# MainLAN_ARM.net
KiCad netlist of a schematic drawn in EAGLE
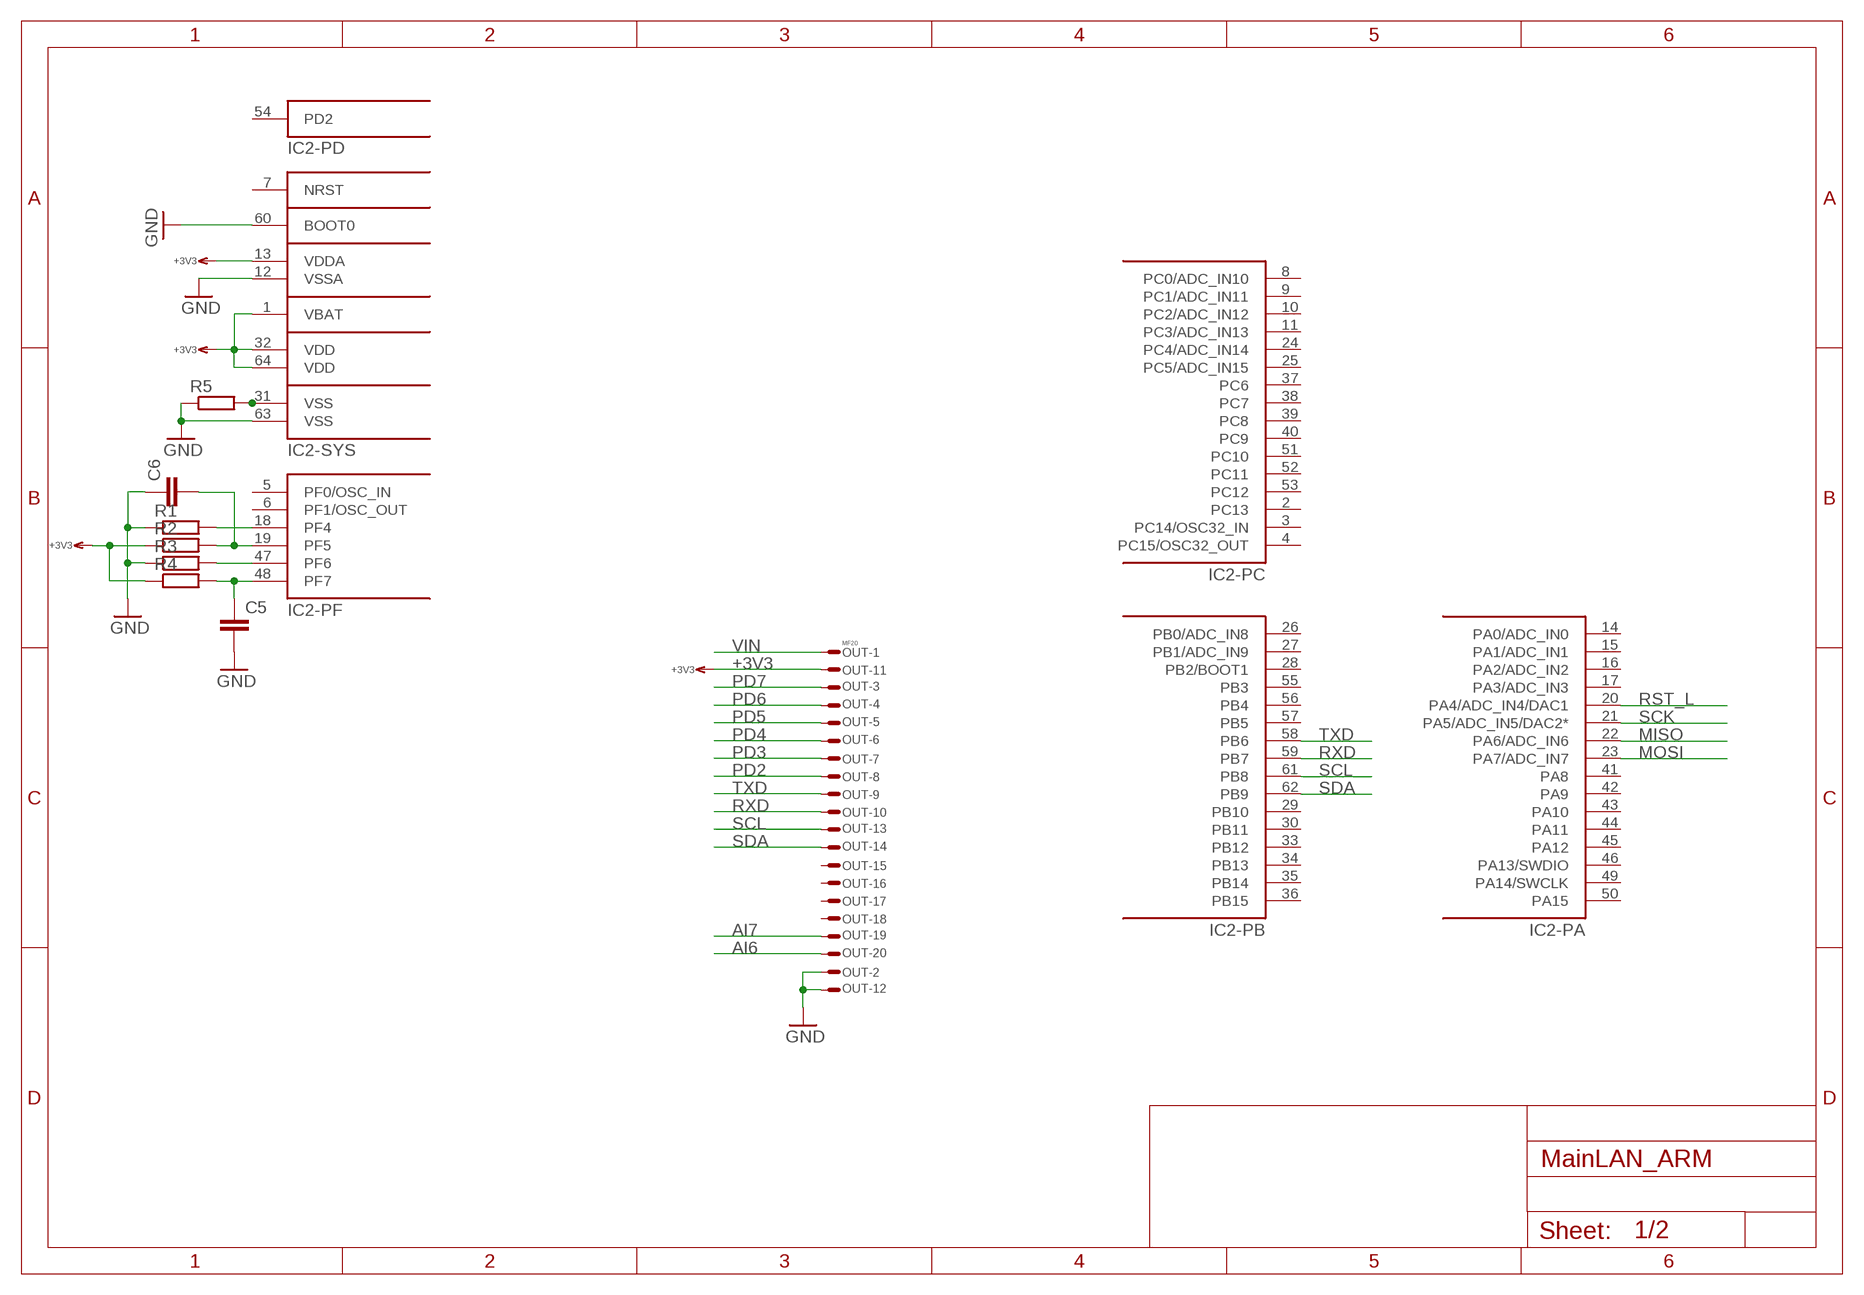
[diagram p0: schematic, sheet 1]
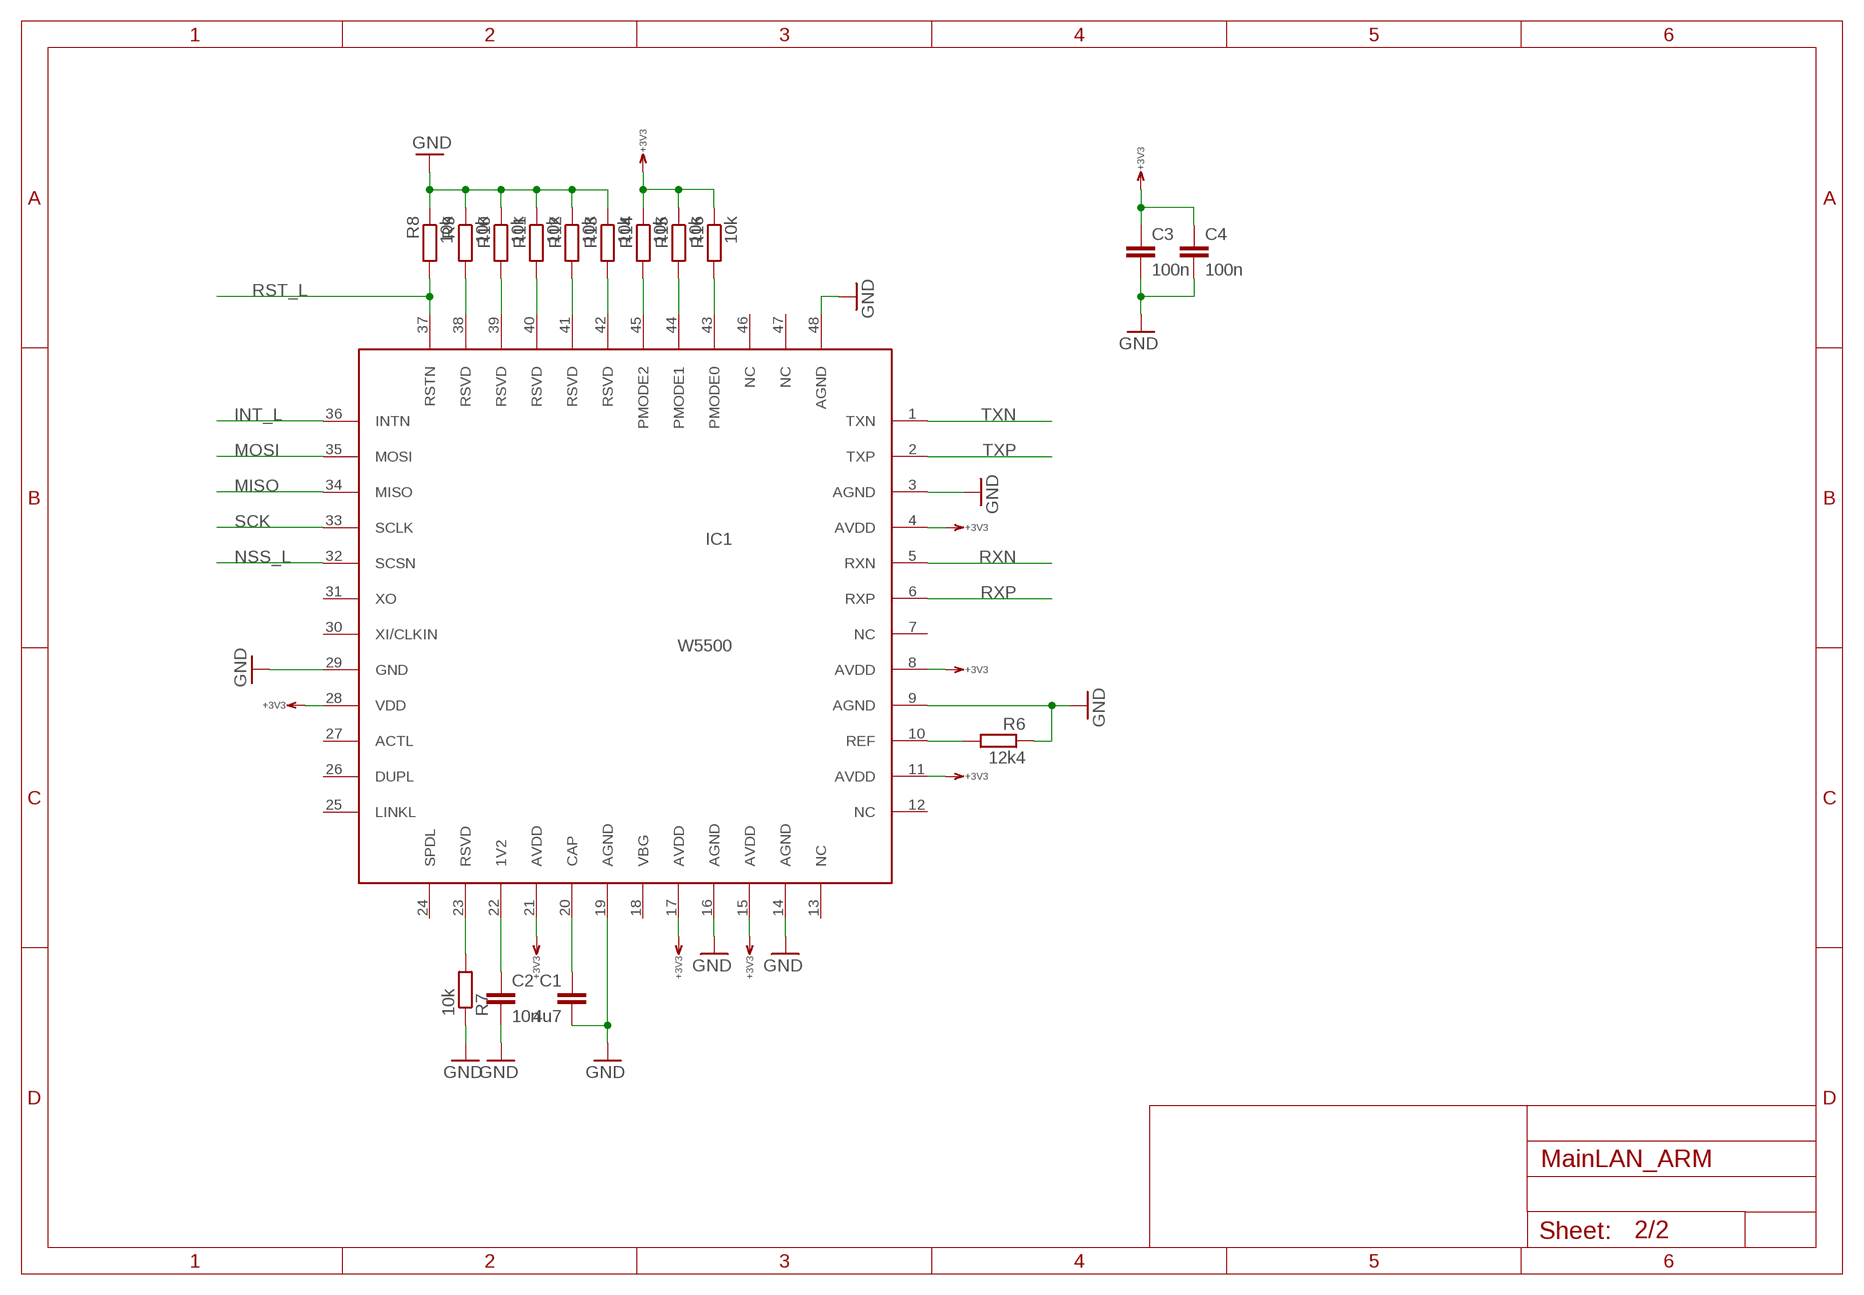
[diagram p1: schematic, sheet 2]

(export (version "E")
  (design (tool "Eeschema 10.0.6"))
  (components
    (comp (ref "C1")
      (value "4u7")
      (footprint "eagle-import:0402")
      (libsource (lib "eagle-import") (part "C0402"))
    )
    (comp (ref "C2")
      (value "10n")
      (footprint "eagle-import:0402")
      (libsource (lib "eagle-import") (part "C0402"))
    )
    (comp (ref "C3")
      (value "100n")
      (footprint "eagle-import:0402")
      (libsource (lib "eagle-import") (part "C0402"))
    )
    (comp (ref "C4")
      (value "100n")
      (footprint "eagle-import:0402")
      (libsource (lib "eagle-import") (part "C0402"))
    )
    (comp (ref "IC1")
      (value "W5500")
      (footprint "eagle-import:LQFP48")
      (libsource (lib "eagle-import") (part "W5500"))
    )
    (comp (ref "R6")
      (value "12k4")
      (footprint "eagle-import:0402")
      (libsource (lib "eagle-import") (part "R0402"))
    )
    (comp (ref "R7")
      (value "10k")
      (footprint "eagle-import:0402")
      (libsource (lib "eagle-import") (part "R0402"))
    )
    (comp (ref "R8")
      (value "10k")
      (footprint "eagle-import:0402")
      (libsource (lib "eagle-import") (part "R0402"))
    )
    (comp (ref "R9")
      (value "10k")
      (footprint "eagle-import:0402")
      (libsource (lib "eagle-import") (part "R0402"))
    )
    (comp (ref "R10")
      (value "10k")
      (footprint "eagle-import:0402")
      (libsource (lib "eagle-import") (part "R0402"))
    )
    (comp (ref "R11")
      (value "10k")
      (footprint "eagle-import:0402")
      (libsource (lib "eagle-import") (part "R0402"))
    )
    (comp (ref "R12")
      (value "10k")
      (footprint "eagle-import:0402")
      (libsource (lib "eagle-import") (part "R0402"))
    )
    (comp (ref "R13")
      (value "10k")
      (footprint "eagle-import:0402")
      (libsource (lib "eagle-import") (part "R0402"))
    )
    (comp (ref "R14")
      (value "10k")
      (footprint "eagle-import:0402")
      (libsource (lib "eagle-import") (part "R0402"))
    )
    (comp (ref "R15")
      (value "10k")
      (footprint "eagle-import:0402")
      (libsource (lib "eagle-import") (part "R0402"))
    )
    (comp (ref "R16")
      (value "10k")
      (footprint "eagle-import:0402")
      (libsource (lib "eagle-import") (part "R0402"))
    )
    (comp (ref "C5")
      (value "C0402")
      (footprint "eagle-import:0402")
      (libsource (lib "eagle-import") (part "C0402"))
    )
    (comp (ref "C6")
      (value "C0402")
      (footprint "eagle-import:0402")
      (libsource (lib "eagle-import") (part "C0402"))
    )
    (comp (ref "IC2")
      (value "STM32F0__R")
      (footprint "eagle-import:LQFP64")
      (libsource (lib "eagle-import") (part "STM32F0__R"))
    )
    (comp (ref "OUT")
      (value "MF20")
      (footprint "eagle-import:ML20LS")
      (libsource (lib "eagle-import") (part "ML20?ELS"))
    )
    (comp (ref "R1")
      (value "R0402")
      (footprint "eagle-import:0402")
      (libsource (lib "eagle-import") (part "R0402"))
    )
    (comp (ref "R2")
      (value "R0402")
      (footprint "eagle-import:0402")
      (libsource (lib "eagle-import") (part "R0402"))
    )
    (comp (ref "R3")
      (value "R0603")
      (footprint "eagle-import:0603")
      (libsource (lib "eagle-import") (part "R0603"))
    )
    (comp (ref "R4")
      (value "R0603")
      (footprint "eagle-import:0603")
      (libsource (lib "eagle-import") (part "R0603"))
    )
    (comp (ref "R5")
      (value "R0603")
      (footprint "eagle-import:0603")
      (libsource (lib "eagle-import") (part "R0603"))
    )
  )
  (nets
    (net (code "1") (name "+3V3") (class "Default")
      (node (ref "C3") (pin "1") (pinfunction "1_1") (pintype "passive"))
      (node (ref "C4") (pin "1") (pinfunction "1_1") (pintype "passive"))
      (node (ref "IC1") (pin "11") (pinfunction "AVDD_11") (pintype "bidirectional"))
      (node (ref "IC1") (pin "15") (pinfunction "AVDD_15") (pintype "bidirectional"))
      (node (ref "IC1") (pin "17") (pinfunction "AVDD_17") (pintype "bidirectional"))
      (node (ref "IC1") (pin "21") (pinfunction "AVDD_21") (pintype "bidirectional"))
      (node (ref "IC1") (pin "28") (pinfunction "VDD_28") (pintype "bidirectional"))
      (node (ref "IC1") (pin "4") (pinfunction "AVDD_4") (pintype "bidirectional"))
      (node (ref "IC1") (pin "8") (pinfunction "AVDD_8") (pintype "bidirectional"))
      (node (ref "IC2") (pin "1") (pinfunction "VBAT_1") (pintype "bidirectional"))
      (node (ref "IC2") (pin "13") (pinfunction "VDDA_13") (pintype "bidirectional"))
      (node (ref "IC2") (pin "32") (pinfunction "VDD_32") (pintype "bidirectional"))
      (node (ref "IC2") (pin "64") (pinfunction "VDD_64") (pintype "bidirectional"))
      (node (ref "OUT") (pin "P$11") (pinfunction "S_P$11") (pintype "passive"))
      (node (ref "R14") (pin "1") (pinfunction "1_1") (pintype "passive"))
      (node (ref "R15") (pin "1") (pinfunction "1_1") (pintype "passive"))
      (node (ref "R16") (pin "1") (pinfunction "1_1") (pintype "passive"))
      (node (ref "R2") (pin "1") (pinfunction "1_1") (pintype "passive"))
      (node (ref "R4") (pin "1") (pinfunction "1_1") (pintype "passive"))
    )
    (net (code "2") (name "AI6") (class "Default")
      (node (ref "OUT") (pin "P$20") (pinfunction "S_P$20") (pintype "passive"))
    )
    (net (code "3") (name "AI7") (class "Default")
      (node (ref "OUT") (pin "P$19") (pinfunction "S_P$19") (pintype "passive"))
    )
    (net (code "4") (name "GND") (class "Default")
      (node (ref "C1") (pin "2") (pinfunction "2_2") (pintype "passive"))
      (node (ref "C2") (pin "2") (pinfunction "2_2") (pintype "passive"))
      (node (ref "C3") (pin "2") (pinfunction "2_2") (pintype "passive"))
      (node (ref "C4") (pin "2") (pinfunction "2_2") (pintype "passive"))
      (node (ref "C5") (pin "2") (pinfunction "2_2") (pintype "passive"))
      (node (ref "C6") (pin "1") (pinfunction "1_1") (pintype "passive"))
      (node (ref "IC1") (pin "14") (pinfunction "AGND_14") (pintype "bidirectional"))
      (node (ref "IC1") (pin "16") (pinfunction "AGND_16") (pintype "bidirectional"))
      (node (ref "IC1") (pin "19") (pinfunction "AGND_19") (pintype "bidirectional"))
      (node (ref "IC1") (pin "29") (pinfunction "GND_29") (pintype "bidirectional"))
      (node (ref "IC1") (pin "3") (pinfunction "AGND_3") (pintype "bidirectional"))
      (node (ref "IC1") (pin "48") (pinfunction "AGND_48") (pintype "bidirectional"))
      (node (ref "IC1") (pin "9") (pinfunction "AGND_9") (pintype "bidirectional"))
      (node (ref "IC2") (pin "12") (pinfunction "VSSA_12") (pintype "bidirectional"))
      (node (ref "IC2") (pin "60") (pinfunction "BOOT0_60") (pintype "bidirectional"))
      (node (ref "IC2") (pin "63") (pinfunction "VSS_63") (pintype "bidirectional"))
      (node (ref "OUT") (pin "P$12") (pinfunction "S_P$12") (pintype "passive"))
      (node (ref "OUT") (pin "P$2") (pinfunction "S_P$2") (pintype "passive"))
      (node (ref "R1") (pin "1") (pinfunction "1_1") (pintype "passive"))
      (node (ref "R10") (pin "1") (pinfunction "1_1") (pintype "passive"))
      (node (ref "R11") (pin "1") (pinfunction "1_1") (pintype "passive"))
      (node (ref "R12") (pin "1") (pinfunction "1_1") (pintype "passive"))
      (node (ref "R13") (pin "1") (pinfunction "1_1") (pintype "passive"))
      (node (ref "R3") (pin "1") (pinfunction "1_1") (pintype "passive"))
      (node (ref "R5") (pin "1") (pinfunction "1_1") (pintype "passive"))
      (node (ref "R6") (pin "1") (pinfunction "1_1") (pintype "passive"))
      (node (ref "R7") (pin "1") (pinfunction "1_1") (pintype "passive"))
      (node (ref "R8") (pin "1") (pinfunction "1_1") (pintype "passive"))
      (node (ref "R9") (pin "1") (pinfunction "1_1") (pintype "passive"))
    )
    (net (code "5") (name "INT_L") (class "Default")
      (node (ref "IC1") (pin "36") (pinfunction "INTN_36") (pintype "output"))
    )
    (net (code "6") (name "MISO") (class "Default")
      (node (ref "IC1") (pin "34") (pinfunction "MISO_34") (pintype "output"))
      (node (ref "IC2") (pin "22") (pinfunction "PA6/ADC_IN6_22") (pintype "bidirectional"))
    )
    (net (code "7") (name "MOSI") (class "Default")
      (node (ref "IC1") (pin "35") (pinfunction "MOSI_35") (pintype "input"))
      (node (ref "IC2") (pin "23") (pinfunction "PA7/ADC_IN7_23") (pintype "bidirectional"))
    )
    (net (code "8") (name "NSS_L") (class "Default")
      (node (ref "IC1") (pin "32") (pinfunction "SCSN_32") (pintype "input"))
    )
    (net (code "9") (name "Net-(IC1-1V2)") (class "Default")
      (node (ref "C2") (pin "1") (pinfunction "1_1") (pintype "passive"))
      (node (ref "IC1") (pin "22") (pinfunction "1V2_22") (pintype "bidirectional"))
    )
    (net (code "10") (name "Net-(IC1-CAP)") (class "Default")
      (node (ref "C1") (pin "1") (pinfunction "1_1") (pintype "passive"))
      (node (ref "IC1") (pin "20") (pinfunction "CAP_20") (pintype "output"))
    )
    (net (code "11") (name "Net-(IC1-PMODE0)") (class "Default")
      (node (ref "IC1") (pin "43") (pinfunction "PMODE0_43") (pintype "input"))
      (node (ref "R16") (pin "2") (pinfunction "2_2") (pintype "passive"))
    )
    (net (code "12") (name "Net-(IC1-PMODE1)") (class "Default")
      (node (ref "IC1") (pin "44") (pinfunction "PMODE1_44") (pintype "input"))
      (node (ref "R15") (pin "2") (pinfunction "2_2") (pintype "passive"))
    )
    (net (code "13") (name "Net-(IC1-PMODE2)") (class "Default")
      (node (ref "IC1") (pin "45") (pinfunction "PMODE2_45") (pintype "input"))
      (node (ref "R14") (pin "2") (pinfunction "2_2") (pintype "passive"))
    )
    (net (code "14") (name "Net-(IC1-REF)") (class "Default")
      (node (ref "IC1") (pin "10") (pinfunction "REF_10") (pintype "bidirectional"))
      (node (ref "R6") (pin "2") (pinfunction "2_2") (pintype "passive"))
    )
    (net (code "15") (name "Net-(IC1-RSVD-Pad23)") (class "Default")
      (node (ref "IC1") (pin "23") (pinfunction "RSVD_23") (pintype "input"))
      (node (ref "R7") (pin "2") (pinfunction "2_2") (pintype "passive"))
    )
    (net (code "16") (name "Net-(IC1-RSVD-Pad38)") (class "Default")
      (node (ref "IC1") (pin "38") (pinfunction "RSVD_38") (pintype "input"))
      (node (ref "R9") (pin "2") (pinfunction "2_2") (pintype "passive"))
    )
    (net (code "17") (name "Net-(IC1-RSVD-Pad39)") (class "Default")
      (node (ref "IC1") (pin "39") (pinfunction "RSVD_39") (pintype "input"))
      (node (ref "R10") (pin "2") (pinfunction "2_2") (pintype "passive"))
    )
    (net (code "18") (name "Net-(IC1-RSVD-Pad40)") (class "Default")
      (node (ref "IC1") (pin "40") (pinfunction "RSVD_40") (pintype "input"))
      (node (ref "R11") (pin "2") (pinfunction "2_2") (pintype "passive"))
    )
    (net (code "19") (name "Net-(IC1-RSVD-Pad41)") (class "Default")
      (node (ref "IC1") (pin "41") (pinfunction "RSVD_41") (pintype "input"))
      (node (ref "R12") (pin "2") (pinfunction "2_2") (pintype "passive"))
    )
    (net (code "20") (name "Net-(IC1-RSVD-Pad42)") (class "Default")
      (node (ref "IC1") (pin "42") (pinfunction "RSVD_42") (pintype "input"))
      (node (ref "R13") (pin "2") (pinfunction "2_2") (pintype "passive"))
    )
    (net (code "21") (name "Net-(IC2E-PF4)") (class "Default")
      (node (ref "IC2") (pin "18") (pinfunction "PF4_18") (pintype "bidirectional"))
      (node (ref "R1") (pin "2") (pinfunction "2_2") (pintype "passive"))
    )
    (net (code "22") (name "Net-(IC2E-PF5)") (class "Default")
      (node (ref "C6") (pin "2") (pinfunction "2_2") (pintype "passive"))
      (node (ref "IC2") (pin "19") (pinfunction "PF5_19") (pintype "bidirectional"))
      (node (ref "R2") (pin "2") (pinfunction "2_2") (pintype "passive"))
    )
    (net (code "23") (name "Net-(IC2E-PF6)") (class "Default")
      (node (ref "IC2") (pin "47") (pinfunction "PF6_47") (pintype "bidirectional"))
      (node (ref "R3") (pin "2") (pinfunction "2_2") (pintype "passive"))
    )
    (net (code "24") (name "Net-(IC2E-PF7)") (class "Default")
      (node (ref "C5") (pin "1") (pinfunction "1_1") (pintype "passive"))
      (node (ref "IC2") (pin "48") (pinfunction "PF7_48") (pintype "bidirectional"))
      (node (ref "R4") (pin "2") (pinfunction "2_2") (pintype "passive"))
    )
    (net (code "25") (name "Net-(IC2F-VSS-Pad31)") (class "Default")
      (node (ref "IC2") (pin "31") (pinfunction "VSS_31") (pintype "bidirectional"))
      (node (ref "R5") (pin "2") (pinfunction "2_2") (pintype "passive"))
    )
    (net (code "26") (name "PD2") (class "Default")
      (node (ref "OUT") (pin "P$8") (pinfunction "S_P$8") (pintype "passive"))
    )
    (net (code "27") (name "PD3") (class "Default")
      (node (ref "OUT") (pin "P$7") (pinfunction "S_P$7") (pintype "passive"))
    )
    (net (code "28") (name "PD4") (class "Default")
      (node (ref "OUT") (pin "P$6") (pinfunction "S_P$6") (pintype "passive"))
    )
    (net (code "29") (name "PD5") (class "Default")
      (node (ref "OUT") (pin "P$5") (pinfunction "S_P$5") (pintype "passive"))
    )
    (net (code "30") (name "PD6") (class "Default")
      (node (ref "OUT") (pin "P$4") (pinfunction "S_P$4") (pintype "passive"))
    )
    (net (code "31") (name "PD7") (class "Default")
      (node (ref "OUT") (pin "P$3") (pinfunction "S_P$3") (pintype "passive"))
    )
    (net (code "32") (name "RST_L") (class "Default")
      (node (ref "IC1") (pin "37") (pinfunction "RSTN_37") (pintype "input"))
      (node (ref "IC2") (pin "20") (pinfunction "PA4/ADC_IN4/DAC1_20") (pintype "bidirectional"))
      (node (ref "R8") (pin "2") (pinfunction "2_2") (pintype "passive"))
    )
    (net (code "33") (name "RXD") (class "Default")
      (node (ref "IC2") (pin "59") (pinfunction "PB7_59") (pintype "bidirectional"))
      (node (ref "OUT") (pin "P$10") (pinfunction "S_P$10") (pintype "passive"))
    )
    (net (code "34") (name "RXN") (class "Default")
      (node (ref "IC1") (pin "5") (pinfunction "RXN_5") (pintype "input"))
    )
    (net (code "35") (name "RXP") (class "Default")
      (node (ref "IC1") (pin "6") (pinfunction "RXP_6") (pintype "input"))
    )
    (net (code "36") (name "SCK") (class "Default")
      (node (ref "IC1") (pin "33") (pinfunction "SCLK_33") (pintype "input"))
      (node (ref "IC2") (pin "21") (pinfunction "PA5/ADC_IN5/DAC2*_21") (pintype "bidirectional"))
    )
    (net (code "37") (name "SCL") (class "Default")
      (node (ref "IC2") (pin "61") (pinfunction "PB8_61") (pintype "bidirectional"))
      (node (ref "OUT") (pin "P$13") (pinfunction "S_P$13") (pintype "passive"))
    )
    (net (code "38") (name "SDA") (class "Default")
      (node (ref "IC2") (pin "62") (pinfunction "PB9_62") (pintype "bidirectional"))
      (node (ref "OUT") (pin "P$14") (pinfunction "S_P$14") (pintype "passive"))
    )
    (net (code "39") (name "TXD") (class "Default")
      (node (ref "IC2") (pin "58") (pinfunction "PB6_58") (pintype "bidirectional"))
      (node (ref "OUT") (pin "P$9") (pinfunction "S_P$9") (pintype "passive"))
    )
    (net (code "40") (name "TXN") (class "Default")
      (node (ref "IC1") (pin "1") (pinfunction "TXN_1") (pintype "output"))
    )
    (net (code "41") (name "TXP") (class "Default")
      (node (ref "IC1") (pin "2") (pinfunction "TXP_2") (pintype "output"))
    )
    (net (code "42") (name "VIN") (class "Default")
      (node (ref "OUT") (pin "P$1") (pinfunction "S_P$1") (pintype "passive"))
    )
    (net (code "43") (name "unconnected-(IC1-ACTL-Pad27)") (class "Default")
      (node (ref "IC1") (pin "27") (pinfunction "ACTL_27") (pintype "output"))
    )
    (net (code "44") (name "unconnected-(IC1-DUPL-Pad26)") (class "Default")
      (node (ref "IC1") (pin "26") (pinfunction "DUPL_26") (pintype "output"))
    )
    (net (code "45") (name "unconnected-(IC1-LINKL-Pad25)") (class "Default")
      (node (ref "IC1") (pin "25") (pinfunction "LINKL_25") (pintype "output"))
    )
    (net (code "46") (name "unconnected-(IC1-NC-Pad7)") (class "Default")
      (node (ref "IC1") (pin "7") (pinfunction "NC_7") (pintype "no_connect"))
    )
    (net (code "47") (name "unconnected-(IC1-NC-Pad12)") (class "Default")
      (node (ref "IC1") (pin "12") (pinfunction "NC_12") (pintype "no_connect"))
    )
    (net (code "48") (name "unconnected-(IC1-NC-Pad13)") (class "Default")
      (node (ref "IC1") (pin "13") (pinfunction "NC_13") (pintype "no_connect"))
    )
    (net (code "49") (name "unconnected-(IC1-NC-Pad46)") (class "Default")
      (node (ref "IC1") (pin "46") (pinfunction "NC_46") (pintype "no_connect"))
    )
    (net (code "50") (name "unconnected-(IC1-NC-Pad47)") (class "Default")
      (node (ref "IC1") (pin "47") (pinfunction "NC_47") (pintype "no_connect"))
    )
    (net (code "51") (name "unconnected-(IC1-SPDL-Pad24)") (class "Default")
      (node (ref "IC1") (pin "24") (pinfunction "SPDL_24") (pintype "output"))
    )
    (net (code "52") (name "unconnected-(IC1-VBG-Pad18)") (class "Default")
      (node (ref "IC1") (pin "18") (pinfunction "VBG_18") (pintype "output"))
    )
    (net (code "53") (name "unconnected-(IC1-XI{slash}CLKIN-Pad30)") (class "Default")
      (node (ref "IC1") (pin "30") (pinfunction "XI/CLKIN_30") (pintype "input"))
    )
    (net (code "54") (name "unconnected-(IC1-XO-Pad31)") (class "Default")
      (node (ref "IC1") (pin "31") (pinfunction "XO_31") (pintype "output"))
    )
    (net (code "55") (name "unconnected-(IC2A-PA0{slash}ADC_IN0-Pad14)") (class "Default")
      (node (ref "IC2") (pin "14") (pinfunction "PA0/ADC_IN0_14") (pintype "bidirectional"))
    )
    (net (code "56") (name "unconnected-(IC2A-PA1{slash}ADC_IN1-Pad15)") (class "Default")
      (node (ref "IC2") (pin "15") (pinfunction "PA1/ADC_IN1_15") (pintype "bidirectional"))
    )
    (net (code "57") (name "unconnected-(IC2A-PA2{slash}ADC_IN2-Pad16)") (class "Default")
      (node (ref "IC2") (pin "16") (pinfunction "PA2/ADC_IN2_16") (pintype "bidirectional"))
    )
    (net (code "58") (name "unconnected-(IC2A-PA3{slash}ADC_IN3-Pad17)") (class "Default")
      (node (ref "IC2") (pin "17") (pinfunction "PA3/ADC_IN3_17") (pintype "bidirectional"))
    )
    (net (code "59") (name "unconnected-(IC2A-PA8-Pad41)") (class "Default")
      (node (ref "IC2") (pin "41") (pinfunction "PA8_41") (pintype "bidirectional"))
    )
    (net (code "60") (name "unconnected-(IC2A-PA9-Pad42)") (class "Default")
      (node (ref "IC2") (pin "42") (pinfunction "PA9_42") (pintype "bidirectional"))
    )
    (net (code "61") (name "unconnected-(IC2A-PA10-Pad43)") (class "Default")
      (node (ref "IC2") (pin "43") (pinfunction "PA10_43") (pintype "bidirectional"))
    )
    (net (code "62") (name "unconnected-(IC2A-PA11-Pad44)") (class "Default")
      (node (ref "IC2") (pin "44") (pinfunction "PA11_44") (pintype "bidirectional"))
    )
    (net (code "63") (name "unconnected-(IC2A-PA12-Pad45)") (class "Default")
      (node (ref "IC2") (pin "45") (pinfunction "PA12_45") (pintype "bidirectional"))
    )
    (net (code "64") (name "unconnected-(IC2A-PA13{slash}SWDIO-Pad46)") (class "Default")
      (node (ref "IC2") (pin "46") (pinfunction "PA13/SWDIO_46") (pintype "bidirectional"))
    )
    (net (code "65") (name "unconnected-(IC2A-PA14{slash}SWCLK-Pad49)") (class "Default")
      (node (ref "IC2") (pin "49") (pinfunction "PA14/SWCLK_49") (pintype "bidirectional"))
    )
    (net (code "66") (name "unconnected-(IC2A-PA15-Pad50)") (class "Default")
      (node (ref "IC2") (pin "50") (pinfunction "PA15_50") (pintype "bidirectional"))
    )
    (net (code "67") (name "unconnected-(IC2B-PB0{slash}ADC_IN8-Pad26)") (class "Default")
      (node (ref "IC2") (pin "26") (pinfunction "PB0/ADC_IN8_26") (pintype "bidirectional"))
    )
    (net (code "68") (name "unconnected-(IC2B-PB1{slash}ADC_IN9-Pad27)") (class "Default")
      (node (ref "IC2") (pin "27") (pinfunction "PB1/ADC_IN9_27") (pintype "bidirectional"))
    )
    (net (code "69") (name "unconnected-(IC2B-PB2{slash}BOOT1-Pad28)") (class "Default")
      (node (ref "IC2") (pin "28") (pinfunction "PB2/BOOT1_28") (pintype "bidirectional"))
    )
    (net (code "70") (name "unconnected-(IC2B-PB3-Pad55)") (class "Default")
      (node (ref "IC2") (pin "55") (pinfunction "PB3_55") (pintype "bidirectional"))
    )
    (net (code "71") (name "unconnected-(IC2B-PB4-Pad56)") (class "Default")
      (node (ref "IC2") (pin "56") (pinfunction "PB4_56") (pintype "bidirectional"))
    )
    (net (code "72") (name "unconnected-(IC2B-PB5-Pad57)") (class "Default")
      (node (ref "IC2") (pin "57") (pinfunction "PB5_57") (pintype "bidirectional"))
    )
    (net (code "73") (name "unconnected-(IC2B-PB10-Pad29)") (class "Default")
      (node (ref "IC2") (pin "29") (pinfunction "PB10_29") (pintype "bidirectional"))
    )
    (net (code "74") (name "unconnected-(IC2B-PB11-Pad30)") (class "Default")
      (node (ref "IC2") (pin "30") (pinfunction "PB11_30") (pintype "bidirectional"))
    )
    (net (code "75") (name "unconnected-(IC2B-PB12-Pad33)") (class "Default")
      (node (ref "IC2") (pin "33") (pinfunction "PB12_33") (pintype "bidirectional"))
    )
    (net (code "76") (name "unconnected-(IC2B-PB13-Pad34)") (class "Default")
      (node (ref "IC2") (pin "34") (pinfunction "PB13_34") (pintype "bidirectional"))
    )
    (net (code "77") (name "unconnected-(IC2B-PB14-Pad35)") (class "Default")
      (node (ref "IC2") (pin "35") (pinfunction "PB14_35") (pintype "bidirectional"))
    )
    (net (code "78") (name "unconnected-(IC2B-PB15-Pad36)") (class "Default")
      (node (ref "IC2") (pin "36") (pinfunction "PB15_36") (pintype "bidirectional"))
    )
    (net (code "79") (name "unconnected-(IC2C-PC0{slash}ADC_IN10-Pad8)") (class "Default")
      (node (ref "IC2") (pin "8") (pinfunction "PC0/ADC_IN10_8") (pintype "bidirectional"))
    )
    (net (code "80") (name "unconnected-(IC2C-PC1{slash}ADC_IN11-Pad9)") (class "Default")
      (node (ref "IC2") (pin "9") (pinfunction "PC1/ADC_IN11_9") (pintype "bidirectional"))
    )
    (net (code "81") (name "unconnected-(IC2C-PC2{slash}ADC_IN12-Pad10)") (class "Default")
      (node (ref "IC2") (pin "10") (pinfunction "PC2/ADC_IN12_10") (pintype "bidirectional"))
    )
    (net (code "82") (name "unconnected-(IC2C-PC3{slash}ADC_IN13-Pad11)") (class "Default")
      (node (ref "IC2") (pin "11") (pinfunction "PC3/ADC_IN13_11") (pintype "bidirectional"))
    )
    (net (code "83") (name "unconnected-(IC2C-PC4{slash}ADC_IN14-Pad24)") (class "Default")
      (node (ref "IC2") (pin "24") (pinfunction "PC4/ADC_IN14_24") (pintype "bidirectional"))
    )
    (net (code "84") (name "unconnected-(IC2C-PC5{slash}ADC_IN15-Pad25)") (class "Default")
      (node (ref "IC2") (pin "25") (pinfunction "PC5/ADC_IN15_25") (pintype "bidirectional"))
    )
    (net (code "85") (name "unconnected-(IC2C-PC6-Pad37)") (class "Default")
      (node (ref "IC2") (pin "37") (pinfunction "PC6_37") (pintype "bidirectional"))
    )
    (net (code "86") (name "unconnected-(IC2C-PC7-Pad38)") (class "Default")
      (node (ref "IC2") (pin "38") (pinfunction "PC7_38") (pintype "bidirectional"))
    )
    (net (code "87") (name "unconnected-(IC2C-PC8-Pad39)") (class "Default")
      (node (ref "IC2") (pin "39") (pinfunction "PC8_39") (pintype "bidirectional"))
    )
    (net (code "88") (name "unconnected-(IC2C-PC9-Pad40)") (class "Default")
      (node (ref "IC2") (pin "40") (pinfunction "PC9_40") (pintype "bidirectional"))
    )
    (net (code "89") (name "unconnected-(IC2C-PC10-Pad51)") (class "Default")
      (node (ref "IC2") (pin "51") (pinfunction "PC10_51") (pintype "bidirectional"))
    )
    (net (code "90") (name "unconnected-(IC2C-PC11-Pad52)") (class "Default")
      (node (ref "IC2") (pin "52") (pinfunction "PC11_52") (pintype "bidirectional"))
    )
    (net (code "91") (name "unconnected-(IC2C-PC12-Pad53)") (class "Default")
      (node (ref "IC2") (pin "53") (pinfunction "PC12_53") (pintype "bidirectional"))
    )
    (net (code "92") (name "unconnected-(IC2C-PC13-Pad2)") (class "Default")
      (node (ref "IC2") (pin "2") (pinfunction "PC13_2") (pintype "bidirectional"))
    )
    (net (code "93") (name "unconnected-(IC2C-PC14{slash}OSC32_IN-Pad3)") (class "Default")
      (node (ref "IC2") (pin "3") (pinfunction "PC14/OSC32_IN_3") (pintype "bidirectional"))
    )
    (net (code "94") (name "unconnected-(IC2C-PC15{slash}OSC32_OUT-Pad4)") (class "Default")
      (node (ref "IC2") (pin "4") (pinfunction "PC15/OSC32_OUT_4") (pintype "bidirectional"))
    )
    (net (code "95") (name "unconnected-(IC2D-PD2-Pad54)") (class "Default")
      (node (ref "IC2") (pin "54") (pinfunction "PD2_54") (pintype "bidirectional"))
    )
    (net (code "96") (name "unconnected-(IC2E-PF0{slash}OSC_IN-Pad5)") (class "Default")
      (node (ref "IC2") (pin "5") (pinfunction "PF0/OSC_IN_5") (pintype "bidirectional"))
    )
    (net (code "97") (name "unconnected-(IC2E-PF1{slash}OSC_OUT-Pad6)") (class "Default")
      (node (ref "IC2") (pin "6") (pinfunction "PF1/OSC_OUT_6") (pintype "bidirectional"))
    )
    (net (code "98") (name "unconnected-(IC2F-NRST-Pad7)") (class "Default")
      (node (ref "IC2") (pin "7") (pinfunction "NRST_7") (pintype "bidirectional"))
    )
    (net (code "99") (name "unconnected-(OUTG-S-PadP$15)") (class "Default")
      (node (ref "OUT") (pin "P$15") (pinfunction "S_P$15") (pintype "passive"))
    )
    (net (code "100") (name "unconnected-(OUTH-S-PadP$16)") (class "Default")
      (node (ref "OUT") (pin "P$16") (pinfunction "S_P$16") (pintype "passive"))
    )
    (net (code "101") (name "unconnected-(OUTI-S-PadP$17)") (class "Default")
      (node (ref "OUT") (pin "P$17") (pinfunction "S_P$17") (pintype "passive"))
    )
    (net (code "102") (name "unconnected-(OUTJ-S-PadP$18)") (class "Default")
      (node (ref "OUT") (pin "P$18") (pinfunction "S_P$18") (pintype "passive"))
    )
  )
)
